# Transfer_V1_Sch.net
KiCad netlist of a schematic drawn in Altium Designer
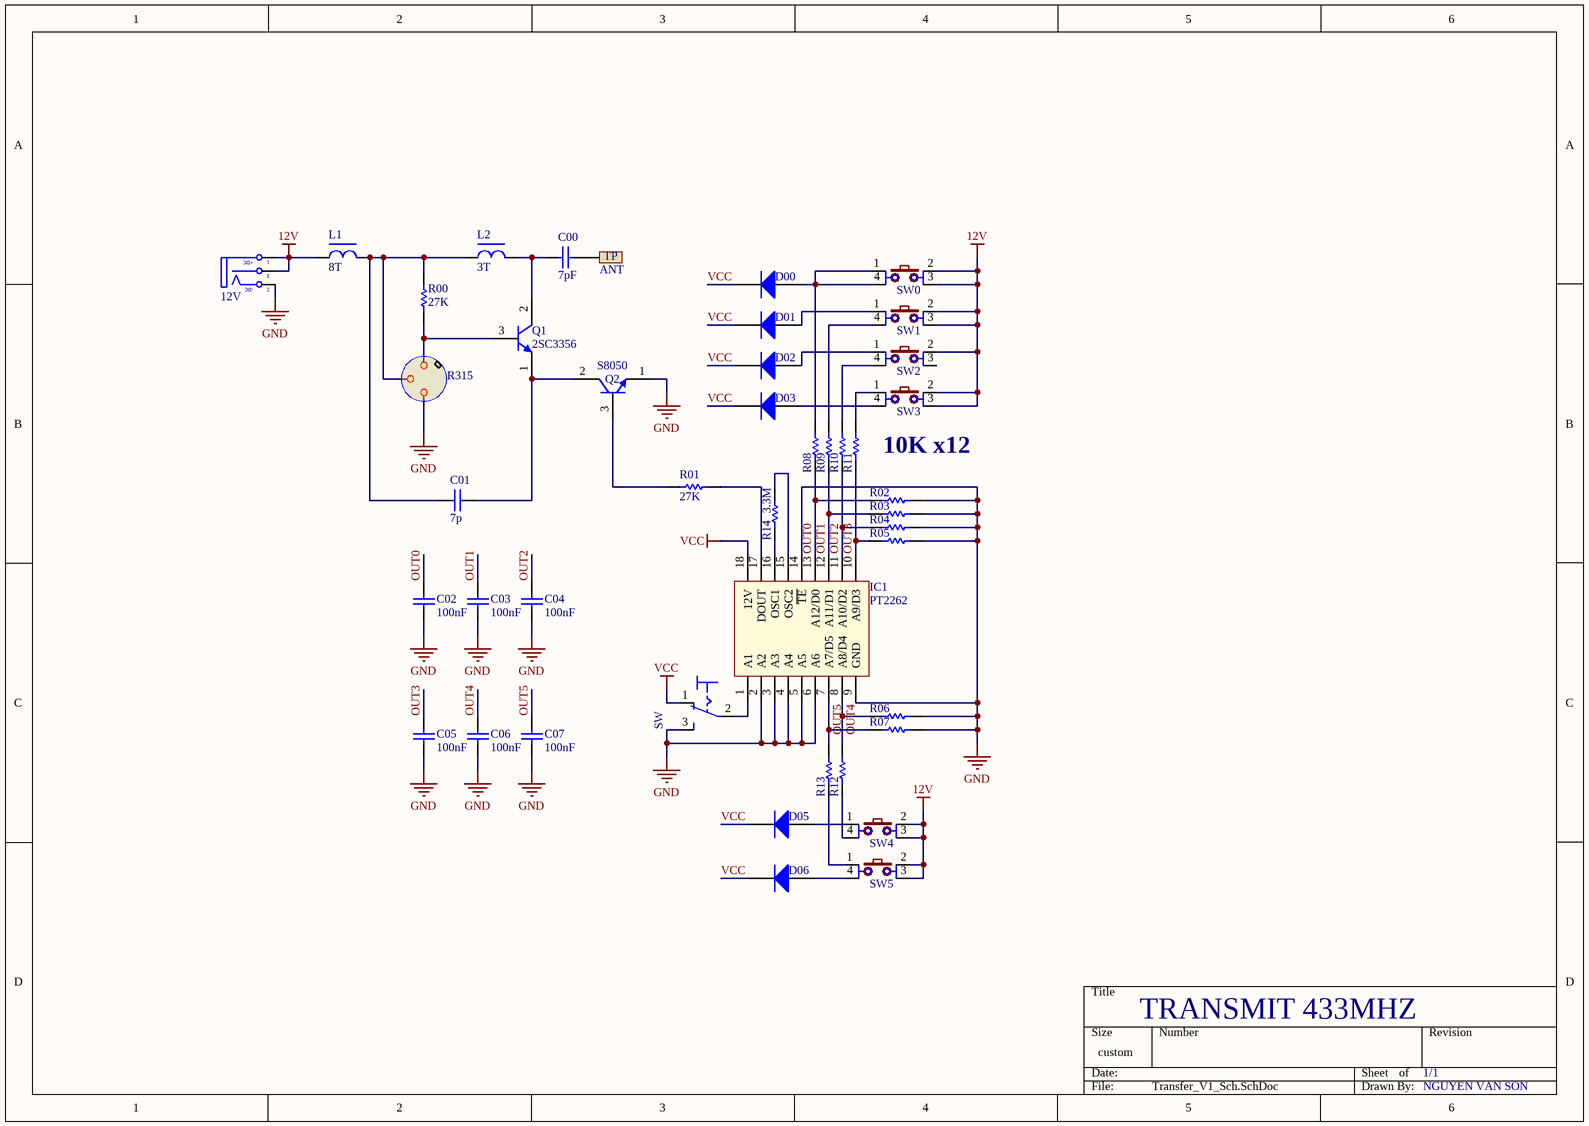
[diagram p0: Transfer_V1_Sch.SchDoc]

(export (version "E")
  (design (tool "Eeschema 10.0.6"))
  (components
    (comp (ref "12V")
      (value "JACK DC 5.5")
      (footprint "JACK DC 5.5")
      (libsource (lib "Altium_Lib_by_KhueNguyenCreator") (part "JACK DC 5.5"))
    )
    (comp (ref "ANT")
      (value "Test Point")
      (footprint "TP")
      (libsource (lib "PIF_Library") (part "Test Point"))
    )
    (comp (ref "C00")
      (value "7pF")
      (footprint "CAP-SM-0805")
      (description "Capacitor")
      (fields (field (name "Comment") "Cap Non-Pol SMD"))
      (libsource (lib "PIF_Library") (part "Cap Non-Pol SMD"))
    )
    (comp (ref "C01")
      (value "7p")
      (footprint "CAP-SM-0603")
      (description "Capacitor")
      (fields (field (name "Comment") "Cap Non-Pol SMD"))
      (libsource (lib "PIF_Library") (part "Cap Non-Pol SMD"))
    )
    (comp (ref "C02")
      (value "100nF")
      (footprint "CAP-SM-0603")
      (description "Capacitor")
      (fields (field (name "Comment") "Cap Non-Pol SMD"))
      (libsource (lib "PIF_Library") (part "Cap Non-Pol SMD"))
    )
    (comp (ref "C03")
      (value "100nF")
      (footprint "CAP-SM-0603")
      (description "Capacitor")
      (fields (field (name "Comment") "Cap Non-Pol SMD"))
      (libsource (lib "PIF_Library") (part "Cap Non-Pol SMD"))
    )
    (comp (ref "C04")
      (value "100nF")
      (footprint "CAP-SM-0603")
      (description "Capacitor")
      (fields (field (name "Comment") "Cap Non-Pol SMD"))
      (libsource (lib "PIF_Library") (part "Cap Non-Pol SMD"))
    )
    (comp (ref "C05")
      (value "100nF")
      (footprint "CAP-SM-0603")
      (description "Capacitor")
      (fields (field (name "Comment") "Cap Non-Pol SMD"))
      (libsource (lib "PIF_Library") (part "Cap Non-Pol SMD"))
    )
    (comp (ref "C06")
      (value "100nF")
      (footprint "CAP-SM-0603")
      (description "Capacitor")
      (fields (field (name "Comment") "Cap Non-Pol SMD"))
      (libsource (lib "PIF_Library") (part "Cap Non-Pol SMD"))
    )
    (comp (ref "C07")
      (value "100nF")
      (footprint "CAP-SM-0603")
      (description "Capacitor")
      (fields (field (name "Comment") "Cap Non-Pol SMD"))
      (libsource (lib "PIF_Library") (part "Cap Non-Pol SMD"))
    )
    (comp (ref "D00")
      (value "M7")
      (footprint "DIODE SMA")
      (description "Dán")
      (libsource (lib "Altium_Lib_by_KhueNguyenCreator") (part "Diode M7 ( 4007 )"))
    )
    (comp (ref "D01")
      (value "M7")
      (footprint "DIODE SMA")
      (description "Dán")
      (libsource (lib "Altium_Lib_by_KhueNguyenCreator") (part "Diode M7 ( 4007 )"))
    )
    (comp (ref "D02")
      (value "M7")
      (footprint "DIODE SMA")
      (description "Dán")
      (libsource (lib "Altium_Lib_by_KhueNguyenCreator") (part "Diode M7 ( 4007 )"))
    )
    (comp (ref "D03")
      (value "M7")
      (footprint "DIODE SMA")
      (description "Dán")
      (libsource (lib "Altium_Lib_by_KhueNguyenCreator") (part "Diode M7 ( 4007 )"))
    )
    (comp (ref "D05")
      (value "M7")
      (footprint "DIODE SMA")
      (description "Dán")
      (libsource (lib "Altium_Lib_by_KhueNguyenCreator") (part "Diode M7 ( 4007 )"))
    )
    (comp (ref "D06")
      (value "M7")
      (footprint "DIODE SMA")
      (description "Dán")
      (libsource (lib "Altium_Lib_by_KhueNguyenCreator") (part "Diode M7 ( 4007 )"))
    )
    (comp (ref "IC1")
      (value "PT2262")
      (footprint "DIP18")
      (description "Remote Control Encoder")
      (libsource (lib "TechMT.VN_Lib_Project v2") (part "PT2262"))
    )
    (comp (ref "L1")
      (value "8T")
      (footprint "L-DIP-M-5.3")
      (description "Inductor")
      (libsource (lib "TechMT.VN_Lib_Project v2") (part "L-DIP-1"))
    )
    (comp (ref "L2")
      (value "3T")
      (footprint "L-DIP-M-5.3")
      (description "Inductor")
      (libsource (lib "TechMT.VN_Lib_Project v2") (part "L-DIP-1"))
    )
    (comp (ref "Q1")
      (value "2SC3356")
      (footprint "SOT23B")
      (description "NPN Bipolar Transistor")
      (libsource (lib "PIF_Library") (part "C1815"))
    )
    (comp (ref "Q2")
      (value "S8050")
      (footprint "SOT23B")
      (description "NPN Bipolar Transistor")
      (libsource (lib "PIF_Library") (part "C1815"))
    )
    (comp (ref "R00")
      (value "27K")
      (footprint "RES-SM-0603")
      (description "Resistor")
      (libsource (lib "PIF_Library") (part "RESISTOR SMD"))
    )
    (comp (ref "R01")
      (value "27K")
      (footprint "RES-SM-0603")
      (description "Resistor")
      (libsource (lib "PIF_Library") (part "RESISTOR SMD"))
    )
    (comp (ref "R02")
      (value "RESISTOR SMD")
      (footprint "RES-SM-0603")
      (description "Resistor")
      (libsource (lib "PIF_Library") (part "RESISTOR SMD"))
    )
    (comp (ref "R03")
      (value "RESISTOR SMD")
      (footprint "RES-SM-0603")
      (description "Resistor")
      (libsource (lib "PIF_Library") (part "RESISTOR SMD"))
    )
    (comp (ref "R04")
      (value "RESISTOR SMD")
      (footprint "RES-SM-0603")
      (description "Resistor")
      (libsource (lib "PIF_Library") (part "RESISTOR SMD"))
    )
    (comp (ref "R05")
      (value "RESISTOR SMD")
      (footprint "RES-SM-0603")
      (description "Resistor")
      (libsource (lib "PIF_Library") (part "RESISTOR SMD"))
    )
    (comp (ref "R06")
      (value "RESISTOR SMD")
      (footprint "RES-SM-0603")
      (description "Resistor")
      (libsource (lib "PIF_Library") (part "RESISTOR SMD"))
    )
    (comp (ref "R07")
      (value "RESISTOR SMD")
      (footprint "RES-SM-0603")
      (description "Resistor")
      (libsource (lib "PIF_Library") (part "RESISTOR SMD"))
    )
    (comp (ref "R08")
      (value "RESISTOR SMD")
      (footprint "RES-SM-0603")
      (description "Resistor")
      (libsource (lib "PIF_Library") (part "RESISTOR SMD"))
    )
    (comp (ref "R09")
      (value "RESISTOR SMD")
      (footprint "RES-SM-0603")
      (description "Resistor")
      (libsource (lib "PIF_Library") (part "RESISTOR SMD"))
    )
    (comp (ref "R10")
      (value "RESISTOR SMD")
      (footprint "RES-SM-0603")
      (description "Resistor")
      (libsource (lib "PIF_Library") (part "RESISTOR SMD"))
    )
    (comp (ref "R11")
      (value "RESISTOR SMD")
      (footprint "RES-SM-0603")
      (description "Resistor")
      (libsource (lib "PIF_Library") (part "RESISTOR SMD"))
    )
    (comp (ref "R12")
      (value "RESISTOR SMD")
      (footprint "RES-SM-0603")
      (description "Resistor")
      (libsource (lib "PIF_Library") (part "RESISTOR SMD"))
    )
    (comp (ref "R13")
      (value "RESISTOR SMD")
      (footprint "RES-SM-0603")
      (description "Resistor")
      (libsource (lib "PIF_Library") (part "RESISTOR SMD"))
    )
    (comp (ref "R14")
      (value "3.3M")
      (footprint "RES-SM-0805")
      (description "Resistor")
      (fields (field (name "Comment") "RESISTOR SMD"))
      (libsource (lib "PIF_Library") (part "RESISTOR SMD"))
    )
    (comp (ref "R315")
      (value "BXR513A")
      (footprint "BXR315A")
      (description "Xtal For RF")
      (libsource (lib "TechMT.VN_Lib_Project v2") (part "BXR315A"))
    )
    (comp (ref "SW")
      (value "MTS-102")
      (footprint "MTS-102")
      (description "Rectangular Cable Assemblies .100 Mini Mate Single Row Discrete Wire Cable Assembly, Terminal")
      (fields (field (name "MF") "Motorola") (field (name "MP") "MTS102"))
      (libsource (lib "MTS-102") (part "MTS-102"))
    )
    (comp (ref "SW0")
      (value "SW")
      (footprint "SW2-DIP")
      (description "Switch button 4 pin")
      (libsource (lib "TechMT.VN_Lib_Project v2") (part "SW4"))
    )
    (comp (ref "SW1")
      (value "SW")
      (footprint "SW2-DIP")
      (description "Switch button 4 pin")
      (libsource (lib "TechMT.VN_Lib_Project v2") (part "SW4"))
    )
    (comp (ref "SW2")
      (value "SW")
      (footprint "SW2-DIP")
      (description "Switch button 4 pin")
      (libsource (lib "TechMT.VN_Lib_Project v2") (part "SW4"))
    )
    (comp (ref "SW3")
      (value "SW")
      (footprint "SW2-DIP")
      (description "Switch button 4 pin")
      (libsource (lib "TechMT.VN_Lib_Project v2") (part "SW4"))
    )
    (comp (ref "SW4")
      (value "SW")
      (footprint "SW2-DIP")
      (description "Switch button 4 pin")
      (libsource (lib "TechMT.VN_Lib_Project v2") (part "SW4"))
    )
    (comp (ref "SW5")
      (value "SW")
      (footprint "SW2-DIP")
      (description "Switch button 4 pin")
      (libsource (lib "TechMT.VN_Lib_Project v2") (part "SW4"))
    )
  )
  (nets
    (net (code "1") (name "/OUT0") (class "Default")
      (node (ref "C02") (pin "2") (pinfunction "2_2") (pintype "passive"))
      (node (ref "IC1") (pin "13") (pinfunction "A12/D0_13") (pintype "passive"))
      (node (ref "R02") (pin "2") (pinfunction "2_2") (pintype "passive"))
      (node (ref "R08") (pin "1") (pinfunction "1_1") (pintype "passive"))
    )
    (net (code "2") (name "/OUT1") (class "Default")
      (node (ref "C03") (pin "2") (pinfunction "2_2") (pintype "passive"))
      (node (ref "IC1") (pin "12") (pinfunction "A11/D1_12") (pintype "passive"))
      (node (ref "R03") (pin "2") (pinfunction "2_2") (pintype "passive"))
      (node (ref "R09") (pin "1") (pinfunction "1_1") (pintype "passive"))
    )
    (net (code "3") (name "/OUT2") (class "Default")
      (node (ref "C04") (pin "2") (pinfunction "2_2") (pintype "passive"))
      (node (ref "IC1") (pin "11") (pinfunction "A10/D2_11") (pintype "passive"))
      (node (ref "R04") (pin "2") (pinfunction "2_2") (pintype "passive"))
      (node (ref "R10") (pin "1") (pinfunction "1_1") (pintype "passive"))
    )
    (net (code "4") (name "/OUT3") (class "Default")
      (node (ref "C05") (pin "2") (pinfunction "2_2") (pintype "passive"))
      (node (ref "IC1") (pin "10") (pinfunction "A9/D3_10") (pintype "passive"))
      (node (ref "R05") (pin "2") (pinfunction "2_2") (pintype "passive"))
      (node (ref "R11") (pin "1") (pinfunction "1_1") (pintype "passive"))
    )
    (net (code "5") (name "/OUT4") (class "Default")
      (node (ref "C06") (pin "2") (pinfunction "2_2") (pintype "passive"))
      (node (ref "IC1") (pin "8") (pinfunction "A8/D4_8") (pintype "passive"))
      (node (ref "R06") (pin "2") (pinfunction "2_2") (pintype "passive"))
      (node (ref "R12") (pin "1") (pinfunction "1_1") (pintype "passive"))
    )
    (net (code "6") (name "/OUT5") (class "Default")
      (node (ref "C07") (pin "2") (pinfunction "2_2") (pintype "passive"))
      (node (ref "IC1") (pin "7") (pinfunction "A7/D5_7") (pintype "passive"))
      (node (ref "R07") (pin "2") (pinfunction "2_2") (pintype "passive"))
      (node (ref "R13") (pin "1") (pinfunction "1_1") (pintype "passive"))
    )
    (net (code "7") (name "12V") (class "Default")
      (node (ref "12V") (pin "1") (pinfunction "T_1") (pintype "passive"))
      (node (ref "12V") (pin "3") (pinfunction "S_3") (pintype "power_in"))
      (node (ref "L1") (pin "1") (pinfunction "1_1") (pintype "passive"))
      (node (ref "SW0") (pin "2") (pinfunction "2_2") (pintype "passive"))
      (node (ref "SW0") (pin "3") (pinfunction "3_3") (pintype "passive"))
      (node (ref "SW1") (pin "2") (pinfunction "2_2") (pintype "passive"))
      (node (ref "SW1") (pin "3") (pinfunction "3_3") (pintype "passive"))
      (node (ref "SW2") (pin "2") (pinfunction "2_2") (pintype "passive"))
      (node (ref "SW3") (pin "2") (pinfunction "2_2") (pintype "passive"))
      (node (ref "SW3") (pin "3") (pinfunction "3_3") (pintype "passive"))
      (node (ref "SW4") (pin "2") (pinfunction "2_2") (pintype "passive"))
      (node (ref "SW4") (pin "3") (pinfunction "3_3") (pintype "passive"))
      (node (ref "SW5") (pin "2") (pinfunction "2_2") (pintype "passive"))
      (node (ref "SW5") (pin "3") (pinfunction "3_3") (pintype "passive"))
    )
    (net (code "8") (name "GND") (class "Default")
      (node (ref "12V") (pin "2") (pinfunction "TN_2") (pintype "passive"))
      (node (ref "C02") (pin "1") (pinfunction "1_1") (pintype "passive"))
      (node (ref "C03") (pin "1") (pinfunction "1_1") (pintype "passive"))
      (node (ref "C04") (pin "1") (pinfunction "1_1") (pintype "passive"))
      (node (ref "C05") (pin "1") (pinfunction "1_1") (pintype "passive"))
      (node (ref "C06") (pin "1") (pinfunction "1_1") (pintype "passive"))
      (node (ref "C07") (pin "1") (pinfunction "1_1") (pintype "passive"))
      (node (ref "IC1") (pin "14") (pinfunction "~{TE}_14") (pintype "passive"))
      (node (ref "IC1") (pin "2") (pinfunction "A2_2") (pintype "passive"))
      (node (ref "IC1") (pin "3") (pinfunction "A3_3") (pintype "passive"))
      (node (ref "IC1") (pin "4") (pinfunction "A4_4") (pintype "passive"))
      (node (ref "IC1") (pin "5") (pinfunction "A5_5") (pintype "passive"))
      (node (ref "IC1") (pin "6") (pinfunction "A6_6") (pintype "passive"))
      (node (ref "IC1") (pin "9") (pinfunction "GND_9") (pintype "passive"))
      (node (ref "Q2") (pin "1") (pinfunction "E_1") (pintype "passive"))
      (node (ref "R02") (pin "1") (pinfunction "1_1") (pintype "passive"))
      (node (ref "R03") (pin "1") (pinfunction "1_1") (pintype "passive"))
      (node (ref "R04") (pin "1") (pinfunction "1_1") (pintype "passive"))
      (node (ref "R05") (pin "1") (pinfunction "1_1") (pintype "passive"))
      (node (ref "R06") (pin "1") (pinfunction "1_1") (pintype "passive"))
      (node (ref "R07") (pin "1") (pinfunction "1_1") (pintype "passive"))
      (node (ref "R315") (pin "3") (pinfunction "3_3") (pintype "passive"))
      (node (ref "SW") (pin "3") (pinfunction "S_3") (pintype "passive"))
    )
    (net (code "9") (name "Net-(ANT-0)") (class "Default")
      (node (ref "ANT") (pin "TP1") (pinfunction "0_TP1") (pintype "passive"))
      (node (ref "C00") (pin "2") (pinfunction "2_2") (pintype "passive"))
    )
    (net (code "10") (name "Net-(C01-Pad1)") (class "Default")
      (node (ref "C01") (pin "1") (pinfunction "1_1") (pintype "passive"))
      (node (ref "L1") (pin "2") (pinfunction "2_2") (pintype "passive"))
      (node (ref "L2") (pin "1") (pinfunction "1_1") (pintype "passive"))
      (node (ref "R00") (pin "1") (pinfunction "1_1") (pintype "passive"))
      (node (ref "R315") (pin "2") (pinfunction "2_2") (pintype "passive"))
    )
    (net (code "11") (name "Net-(D00-A)") (class "Default")
      (node (ref "D00") (pin "1") (pinfunction "A_1") (pintype "passive"))
      (node (ref "R08") (pin "2") (pinfunction "2_2") (pintype "passive"))
      (node (ref "SW0") (pin "1") (pintype "passive"))
      (node (ref "SW0") (pin "4") (pinfunction "4_4") (pintype "passive"))
    )
    (net (code "12") (name "Net-(D01-A)") (class "Default")
      (node (ref "D01") (pin "1") (pinfunction "A_1") (pintype "passive"))
      (node (ref "SW1") (pin "1") (pintype "passive"))
    )
    (net (code "13") (name "Net-(D02-A)") (class "Default")
      (node (ref "D02") (pin "1") (pinfunction "A_1") (pintype "passive"))
      (node (ref "SW2") (pin "1") (pintype "passive"))
    )
    (net (code "14") (name "Net-(D03-A)") (class "Default")
      (node (ref "D03") (pin "1") (pinfunction "A_1") (pintype "passive"))
      (node (ref "SW3") (pin "4") (pinfunction "4_4") (pintype "passive"))
    )
    (net (code "15") (name "Net-(D05-A)") (class "Default")
      (node (ref "D05") (pin "1") (pinfunction "A_1") (pintype "passive"))
      (node (ref "SW4") (pin "1") (pintype "passive"))
    )
    (net (code "16") (name "Net-(D06-A)") (class "Default")
      (node (ref "D06") (pin "1") (pinfunction "A_1") (pintype "passive"))
      (node (ref "SW5") (pin "4") (pinfunction "4_4") (pintype "passive"))
    )
    (net (code "17") (name "Net-(IC1-A1)") (class "Default")
      (node (ref "IC1") (pin "1") (pinfunction "A1_1") (pintype "passive"))
      (node (ref "SW") (pin "2") (pinfunction "P_2") (pintype "passive"))
    )
    (net (code "18") (name "Net-(IC1-DOUT)") (class "Default")
      (node (ref "IC1") (pin "17") (pinfunction "DOUT_17") (pintype "passive"))
      (node (ref "R01") (pin "2") (pinfunction "2_2") (pintype "passive"))
    )
    (net (code "19") (name "Net-(IC1-OSC1)") (class "Default")
      (node (ref "IC1") (pin "16") (pinfunction "OSC1_16") (pintype "passive"))
      (node (ref "R14") (pin "2") (pinfunction "2_2") (pintype "passive"))
    )
    (net (code "20") (name "Net-(IC1-OSC2)") (class "Default")
      (node (ref "IC1") (pin "15") (pinfunction "OSC2_15") (pintype "passive"))
      (node (ref "R14") (pin "1") (pinfunction "1_1") (pintype "passive"))
    )
    (net (code "21") (name "Net-(Q1-B)") (class "Default")
      (node (ref "Q1") (pin "3") (pinfunction "B_3") (pintype "passive"))
      (node (ref "R00") (pin "2") (pinfunction "2_2") (pintype "passive"))
      (node (ref "R315") (pin "1") (pinfunction "1_1") (pintype "passive"))
    )
    (net (code "22") (name "Net-(Q1-C)") (class "Default")
      (node (ref "C00") (pin "1") (pinfunction "1_1") (pintype "passive"))
      (node (ref "L2") (pin "2") (pinfunction "2_2") (pintype "passive"))
      (node (ref "Q1") (pin "2") (pinfunction "C_2") (pintype "passive"))
    )
    (net (code "23") (name "Net-(Q1-E)") (class "Default")
      (node (ref "C01") (pin "2") (pinfunction "2_2") (pintype "passive"))
      (node (ref "Q1") (pin "1") (pinfunction "E_1") (pintype "passive"))
      (node (ref "Q2") (pin "2") (pinfunction "C_2") (pintype "passive"))
    )
    (net (code "24") (name "Net-(Q2-B)") (class "Default")
      (node (ref "Q2") (pin "3") (pinfunction "B_3") (pintype "passive"))
      (node (ref "R01") (pin "1") (pinfunction "1_1") (pintype "passive"))
    )
    (net (code "25") (name "Net-(R09-Pad2)") (class "Default")
      (node (ref "R09") (pin "2") (pinfunction "2_2") (pintype "passive"))
      (node (ref "SW1") (pin "4") (pinfunction "4_4") (pintype "passive"))
    )
    (net (code "26") (name "Net-(R10-Pad2)") (class "Default")
      (node (ref "R10") (pin "2") (pinfunction "2_2") (pintype "passive"))
      (node (ref "SW2") (pin "4") (pinfunction "4_4") (pintype "passive"))
    )
    (net (code "27") (name "Net-(R11-Pad2)") (class "Default")
      (node (ref "R11") (pin "2") (pinfunction "2_2") (pintype "passive"))
      (node (ref "SW3") (pin "1") (pintype "passive"))
    )
    (net (code "28") (name "Net-(R12-Pad2)") (class "Default")
      (node (ref "R12") (pin "2") (pinfunction "2_2") (pintype "passive"))
      (node (ref "SW4") (pin "4") (pinfunction "4_4") (pintype "passive"))
    )
    (net (code "29") (name "Net-(R13-Pad2)") (class "Default")
      (node (ref "R13") (pin "2") (pinfunction "2_2") (pintype "passive"))
      (node (ref "SW5") (pin "1") (pintype "passive"))
    )
    (net (code "30") (name "VCC") (class "Default")
      (node (ref "D00") (pin "2") (pinfunction "K_2") (pintype "passive"))
      (node (ref "D01") (pin "2") (pinfunction "K_2") (pintype "passive"))
      (node (ref "D02") (pin "2") (pinfunction "K_2") (pintype "passive"))
      (node (ref "D03") (pin "2") (pinfunction "K_2") (pintype "passive"))
      (node (ref "D05") (pin "2") (pinfunction "K_2") (pintype "passive"))
      (node (ref "D06") (pin "2") (pinfunction "K_2") (pintype "passive"))
      (node (ref "IC1") (pin "18") (pinfunction "12V_18") (pintype "passive"))
      (node (ref "SW") (pin "1") (pinfunction "O_1") (pintype "passive"))
    )
    (net (code "31") (name "unconnected-(SW2-Pad3)") (class "Default")
      (node (ref "SW2") (pin "3") (pinfunction "3_3") (pintype "passive"))
    )
  )
)
